# Volterra_MKS_Gen_Daughter_Board.net
KiCad netlist of a schematic drawn in EAGLE
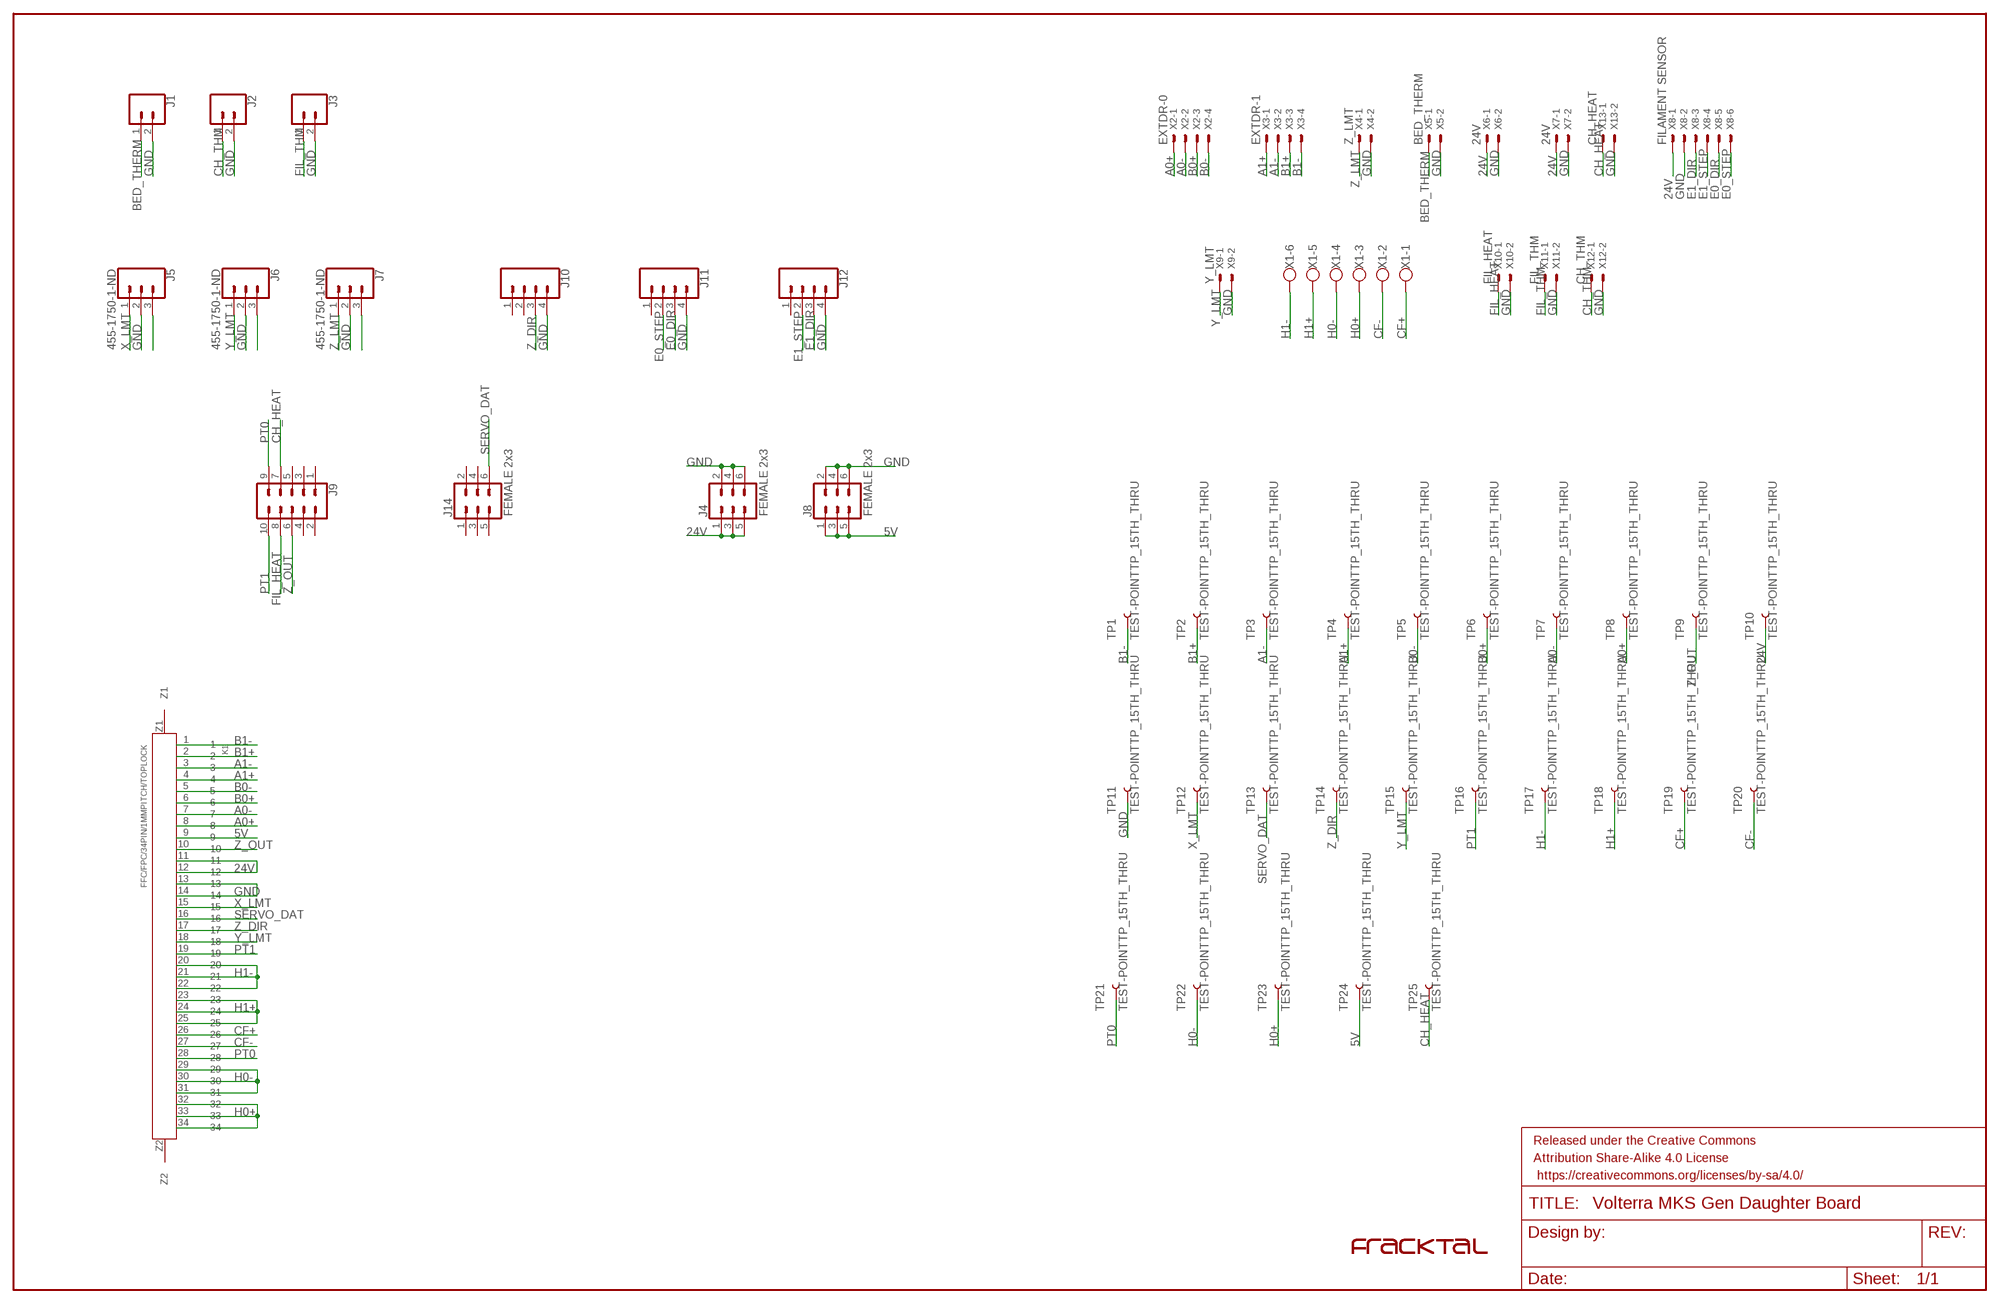
[diagram p0: schematic, sheet 1]

(export (version "E")
  (design (tool "Eeschema 10.0.6"))
  (components
    (comp (ref "FRAME1")
      (value "FRAME-LEDGER")
      (footprint "eagle-import:CREATIVE_COMMONS")
      (libsource (lib "eagle-import") (part "FRAME-LEDGER"))
    )
    (comp (ref "J1")
      (value "CONN_02")
      (footprint "eagle-import:1X02")
      (libsource (lib "eagle-import") (part "CONN_02"))
    )
    (comp (ref "J2")
      (value "CONN_02")
      (footprint "eagle-import:1X02")
      (libsource (lib "eagle-import") (part "CONN_02"))
    )
    (comp (ref "J3")
      (value "CONN_02")
      (footprint "eagle-import:1X02")
      (libsource (lib "eagle-import") (part "CONN_02"))
    )
    (comp (ref "J4")
      (value "FEMALE 2x3")
      (footprint "eagle-import:2X3")
      (libsource (lib "eagle-import") (part "CONN_03X2FEMALE"))
    )
    (comp (ref "J5")
      (value "455-1750-1-ND")
      (footprint "eagle-import:1X03")
      (libsource (lib "eagle-import") (part "CONN_03"))
    )
    (comp (ref "J6")
      (value "455-1750-1-ND")
      (footprint "eagle-import:1X03")
      (libsource (lib "eagle-import") (part "CONN_03"))
    )
    (comp (ref "J7")
      (value "455-1750-1-ND")
      (footprint "eagle-import:1X03")
      (libsource (lib "eagle-import") (part "CONN_03"))
    )
    (comp (ref "J8")
      (value "FEMALE 2x3")
      (footprint "eagle-import:2X3")
      (libsource (lib "eagle-import") (part "CONN_03X2FEMALE"))
    )
    (comp (ref "J9")
      (value "CONN_05X2PTH")
      (footprint "eagle-import:2X5")
      (libsource (lib "eagle-import") (part "CONN_05X2PTH"))
    )
    (comp (ref "J10")
      (value "CONN_04")
      (footprint "eagle-import:1X04")
      (libsource (lib "eagle-import") (part "CONN_04"))
    )
    (comp (ref "J11")
      (value "CONN_04")
      (footprint "eagle-import:1X04")
      (libsource (lib "eagle-import") (part "CONN_04"))
    )
    (comp (ref "J12")
      (value "CONN_04")
      (footprint "eagle-import:1X04")
      (libsource (lib "eagle-import") (part "CONN_04"))
    )
    (comp (ref "J14")
      (value "FEMALE 2x3")
      (footprint "eagle-import:2X3")
      (libsource (lib "eagle-import") (part "CONN_03X2FEMALE"))
    )
    (comp (ref "K1")
      (value "FFC/FPC/34PIN/1MMPITCH/TOPLOCK")
      (footprint "eagle-import:34PIN_1MMPITCH_FFC_FPC")
      (libsource (lib "eagle-import") (part "FFC/FPC/34PIN/1MMPITCH/TOPLOCK"))
    )
    (comp (ref "TP1")
      (value "TEST-POINTTP_15TH_THRU")
      (footprint "eagle-import:TP_15TH")
      (libsource (lib "eagle-import") (part "TEST-POINTTP_15TH_THRU"))
    )
    (comp (ref "TP2")
      (value "TEST-POINTTP_15TH_THRU")
      (footprint "eagle-import:TP_15TH")
      (libsource (lib "eagle-import") (part "TEST-POINTTP_15TH_THRU"))
    )
    (comp (ref "TP3")
      (value "TEST-POINTTP_15TH_THRU")
      (footprint "eagle-import:TP_15TH")
      (libsource (lib "eagle-import") (part "TEST-POINTTP_15TH_THRU"))
    )
    (comp (ref "TP4")
      (value "TEST-POINTTP_15TH_THRU")
      (footprint "eagle-import:TP_15TH")
      (libsource (lib "eagle-import") (part "TEST-POINTTP_15TH_THRU"))
    )
    (comp (ref "TP5")
      (value "TEST-POINTTP_15TH_THRU")
      (footprint "eagle-import:TP_15TH")
      (libsource (lib "eagle-import") (part "TEST-POINTTP_15TH_THRU"))
    )
    (comp (ref "TP6")
      (value "TEST-POINTTP_15TH_THRU")
      (footprint "eagle-import:TP_15TH")
      (libsource (lib "eagle-import") (part "TEST-POINTTP_15TH_THRU"))
    )
    (comp (ref "TP7")
      (value "TEST-POINTTP_15TH_THRU")
      (footprint "eagle-import:TP_15TH")
      (libsource (lib "eagle-import") (part "TEST-POINTTP_15TH_THRU"))
    )
    (comp (ref "TP8")
      (value "TEST-POINTTP_15TH_THRU")
      (footprint "eagle-import:TP_15TH")
      (libsource (lib "eagle-import") (part "TEST-POINTTP_15TH_THRU"))
    )
    (comp (ref "TP9")
      (value "TEST-POINTTP_15TH_THRU")
      (footprint "eagle-import:TP_15TH")
      (libsource (lib "eagle-import") (part "TEST-POINTTP_15TH_THRU"))
    )
    (comp (ref "TP10")
      (value "TEST-POINTTP_15TH_THRU")
      (footprint "eagle-import:TP_15TH")
      (libsource (lib "eagle-import") (part "TEST-POINTTP_15TH_THRU"))
    )
    (comp (ref "TP11")
      (value "TEST-POINTTP_15TH_THRU")
      (footprint "eagle-import:TP_15TH")
      (libsource (lib "eagle-import") (part "TEST-POINTTP_15TH_THRU"))
    )
    (comp (ref "TP12")
      (value "TEST-POINTTP_15TH_THRU")
      (footprint "eagle-import:TP_15TH")
      (libsource (lib "eagle-import") (part "TEST-POINTTP_15TH_THRU"))
    )
    (comp (ref "TP13")
      (value "TEST-POINTTP_15TH_THRU")
      (footprint "eagle-import:TP_15TH")
      (libsource (lib "eagle-import") (part "TEST-POINTTP_15TH_THRU"))
    )
    (comp (ref "TP14")
      (value "TEST-POINTTP_15TH_THRU")
      (footprint "eagle-import:TP_15TH")
      (libsource (lib "eagle-import") (part "TEST-POINTTP_15TH_THRU"))
    )
    (comp (ref "TP15")
      (value "TEST-POINTTP_15TH_THRU")
      (footprint "eagle-import:TP_15TH")
      (libsource (lib "eagle-import") (part "TEST-POINTTP_15TH_THRU"))
    )
    (comp (ref "TP16")
      (value "TEST-POINTTP_15TH_THRU")
      (footprint "eagle-import:TP_15TH")
      (libsource (lib "eagle-import") (part "TEST-POINTTP_15TH_THRU"))
    )
    (comp (ref "TP17")
      (value "TEST-POINTTP_15TH_THRU")
      (footprint "eagle-import:TP_15TH")
      (libsource (lib "eagle-import") (part "TEST-POINTTP_15TH_THRU"))
    )
    (comp (ref "TP18")
      (value "TEST-POINTTP_15TH_THRU")
      (footprint "eagle-import:TP_15TH")
      (libsource (lib "eagle-import") (part "TEST-POINTTP_15TH_THRU"))
    )
    (comp (ref "TP19")
      (value "TEST-POINTTP_15TH_THRU")
      (footprint "eagle-import:TP_15TH")
      (libsource (lib "eagle-import") (part "TEST-POINTTP_15TH_THRU"))
    )
    (comp (ref "TP20")
      (value "TEST-POINTTP_15TH_THRU")
      (footprint "eagle-import:TP_15TH")
      (libsource (lib "eagle-import") (part "TEST-POINTTP_15TH_THRU"))
    )
    (comp (ref "TP21")
      (value "TEST-POINTTP_15TH_THRU")
      (footprint "eagle-import:TP_15TH")
      (libsource (lib "eagle-import") (part "TEST-POINTTP_15TH_THRU"))
    )
    (comp (ref "TP22")
      (value "TEST-POINTTP_15TH_THRU")
      (footprint "eagle-import:TP_15TH")
      (libsource (lib "eagle-import") (part "TEST-POINTTP_15TH_THRU"))
    )
    (comp (ref "TP23")
      (value "TEST-POINTTP_15TH_THRU")
      (footprint "eagle-import:TP_15TH")
      (libsource (lib "eagle-import") (part "TEST-POINTTP_15TH_THRU"))
    )
    (comp (ref "TP24")
      (value "TEST-POINTTP_15TH_THRU")
      (footprint "eagle-import:TP_15TH")
      (libsource (lib "eagle-import") (part "TEST-POINTTP_15TH_THRU"))
    )
    (comp (ref "TP25")
      (value "TEST-POINTTP_15TH_THRU")
      (footprint "eagle-import:TP_15TH")
      (libsource (lib "eagle-import") (part "TEST-POINTTP_15TH_THRU"))
    )
    (comp (ref "U$1")
      (value "FRACKTALLOGO")
      (footprint "eagle-import:FRACKTALLOGO")
      (libsource (lib "eagle-import") (part "FRACKTALLOGO"))
    )
    (comp (ref "X1")
      (value "W237-6")
      (footprint "eagle-import:W237-6")
      (libsource (lib "eagle-import") (part "W237-6"))
    )
    (comp (ref "X2")
      (value "EXTDR-0")
      (footprint "eagle-import:JST-XH-04-PACKAGE-LONG-PAD")
      (libsource (lib "eagle-import") (part "JST-XH-04-PIN-LONG-PAD"))
    )
    (comp (ref "X3")
      (value "EXTDR-1")
      (footprint "eagle-import:JST-XH-04-PACKAGE-LONG-PAD")
      (libsource (lib "eagle-import") (part "JST-XH-04-PIN-LONG-PAD"))
    )
    (comp (ref "X4")
      (value "Z_LMT")
      (footprint "eagle-import:JST-XH-02-PACKAGE-LONG-PAD")
      (libsource (lib "eagle-import") (part "JST-XH-02-PIN-LONG-PAD"))
    )
    (comp (ref "X5")
      (value "BED_THERM")
      (footprint "eagle-import:JST-XH-02-PACKAGE-LONG-PAD")
      (libsource (lib "eagle-import") (part "JST-XH-02-PIN-LONG-PAD"))
    )
    (comp (ref "X6")
      (value "24V")
      (footprint "eagle-import:JST-XH-02-PACKAGE-LONG-PAD")
      (libsource (lib "eagle-import") (part "JST-XH-02-PIN-LONG-PAD"))
    )
    (comp (ref "X7")
      (value "24V")
      (footprint "eagle-import:JST-XH-02-PACKAGE-LONG-PAD")
      (libsource (lib "eagle-import") (part "JST-XH-02-PIN-LONG-PAD"))
    )
    (comp (ref "X8")
      (value "FILAMENT SENSOR")
      (footprint "eagle-import:JST-XH-06-PACKAGE-LONG-PAD")
      (libsource (lib "eagle-import") (part "JST-XH-06-PIN-LONG-PAD"))
    )
    (comp (ref "X9")
      (value "Y_LMT")
      (footprint "eagle-import:JST-XH-02-PACKAGE-LONG-PAD")
      (libsource (lib "eagle-import") (part "JST-XH-02-PIN-LONG-PAD"))
    )
    (comp (ref "X10")
      (value "FIL_HEAT")
      (footprint "eagle-import:JST-XH-02-PACKAGE-LONG-PAD")
      (libsource (lib "eagle-import") (part "JST-XH-02-PIN-LONG-PAD"))
    )
    (comp (ref "X11")
      (value "FIL_THM")
      (footprint "eagle-import:JST-XH-02-PACKAGE-LONG-PAD")
      (libsource (lib "eagle-import") (part "JST-XH-02-PIN-LONG-PAD"))
    )
    (comp (ref "X12")
      (value "CH_THM")
      (footprint "eagle-import:JST-XH-02-PACKAGE-LONG-PAD")
      (libsource (lib "eagle-import") (part "JST-XH-02-PIN-LONG-PAD"))
    )
    (comp (ref "X13")
      (value "CH_HEAT")
      (footprint "eagle-import:JST-XH-02-PACKAGE-LONG-PAD")
      (libsource (lib "eagle-import") (part "JST-XH-02-PIN-LONG-PAD"))
    )
  )
  (nets
    (net (code "1") (name "/5V") (class "Default")
      (node (ref "J8") (pin "1") (pinfunction "1_1") (pintype "bidirectional"))
      (node (ref "J8") (pin "3") (pinfunction "3_3") (pintype "bidirectional"))
      (node (ref "J8") (pin "5") (pinfunction "5_5") (pintype "bidirectional"))
      (node (ref "K1") (pin "9") (pinfunction "9_9") (pintype "bidirectional"))
      (node (ref "TP24") (pin "P$1") (pinfunction "1_P$1") (pintype "bidirectional"))
    )
    (net (code "2") (name "/24V") (class "Default")
      (node (ref "J4") (pin "1") (pinfunction "1_1") (pintype "bidirectional"))
      (node (ref "J4") (pin "3") (pinfunction "3_3") (pintype "bidirectional"))
      (node (ref "J4") (pin "5") (pinfunction "5_5") (pintype "bidirectional"))
      (node (ref "K1") (pin "11") (pinfunction "11_11") (pintype "bidirectional"))
      (node (ref "K1") (pin "12") (pinfunction "12_12") (pintype "bidirectional"))
      (node (ref "TP10") (pin "P$1") (pinfunction "1_P$1") (pintype "bidirectional"))
      (node (ref "X6") (pin "1") (pinfunction "S_1") (pintype "passive"))
      (node (ref "X7") (pin "1") (pinfunction "S_1") (pintype "passive"))
      (node (ref "X8") (pin "1") (pinfunction "S_1") (pintype "passive"))
    )
    (net (code "3") (name "/A0+") (class "Default")
      (node (ref "K1") (pin "8") (pinfunction "8_8") (pintype "bidirectional"))
      (node (ref "TP8") (pin "P$1") (pinfunction "1_P$1") (pintype "bidirectional"))
      (node (ref "X2") (pin "1") (pinfunction "S_1") (pintype "passive"))
    )
    (net (code "4") (name "/A0-") (class "Default")
      (node (ref "K1") (pin "7") (pinfunction "7_7") (pintype "bidirectional"))
      (node (ref "TP7") (pin "P$1") (pinfunction "1_P$1") (pintype "bidirectional"))
      (node (ref "X2") (pin "2") (pinfunction "S_2") (pintype "passive"))
    )
    (net (code "5") (name "/A1+") (class "Default")
      (node (ref "K1") (pin "4") (pinfunction "4_4") (pintype "bidirectional"))
      (node (ref "TP4") (pin "P$1") (pinfunction "1_P$1") (pintype "bidirectional"))
      (node (ref "X3") (pin "1") (pinfunction "S_1") (pintype "passive"))
    )
    (net (code "6") (name "/A1-") (class "Default")
      (node (ref "K1") (pin "3") (pinfunction "3_3") (pintype "bidirectional"))
      (node (ref "TP3") (pin "P$1") (pinfunction "1_P$1") (pintype "bidirectional"))
      (node (ref "X3") (pin "2") (pinfunction "S_2") (pintype "passive"))
    )
    (net (code "7") (name "/B0+") (class "Default")
      (node (ref "K1") (pin "6") (pinfunction "6_6") (pintype "bidirectional"))
      (node (ref "TP6") (pin "P$1") (pinfunction "1_P$1") (pintype "bidirectional"))
      (node (ref "X2") (pin "3") (pinfunction "S_3") (pintype "passive"))
    )
    (net (code "8") (name "/B0-") (class "Default")
      (node (ref "K1") (pin "5") (pinfunction "5_5") (pintype "bidirectional"))
      (node (ref "TP5") (pin "P$1") (pinfunction "1_P$1") (pintype "bidirectional"))
      (node (ref "X2") (pin "4") (pinfunction "S_4") (pintype "passive"))
    )
    (net (code "9") (name "/B1+") (class "Default")
      (node (ref "K1") (pin "2") (pinfunction "2_2") (pintype "bidirectional"))
      (node (ref "TP2") (pin "P$1") (pinfunction "1_P$1") (pintype "bidirectional"))
      (node (ref "X3") (pin "3") (pinfunction "S_3") (pintype "passive"))
    )
    (net (code "10") (name "/B1-") (class "Default")
      (node (ref "K1") (pin "1") (pinfunction "1_1") (pintype "bidirectional"))
      (node (ref "TP1") (pin "P$1") (pinfunction "1_P$1") (pintype "bidirectional"))
      (node (ref "X3") (pin "4") (pinfunction "S_4") (pintype "passive"))
    )
    (net (code "11") (name "/BED_THERM") (class "Default")
      (node (ref "J1") (pin "1") (pinfunction "1_1") (pintype "passive"))
      (node (ref "X5") (pin "1") (pinfunction "S_1") (pintype "passive"))
    )
    (net (code "12") (name "/CF+") (class "Default")
      (node (ref "K1") (pin "26") (pinfunction "26_26") (pintype "bidirectional"))
      (node (ref "TP19") (pin "P$1") (pinfunction "1_P$1") (pintype "bidirectional"))
      (node (ref "X1") (pin "1") (pinfunction "KL_1") (pintype "passive"))
    )
    (net (code "13") (name "/CF-") (class "Default")
      (node (ref "K1") (pin "27") (pinfunction "27_27") (pintype "bidirectional"))
      (node (ref "TP20") (pin "P$1") (pinfunction "1_P$1") (pintype "bidirectional"))
      (node (ref "X1") (pin "2") (pinfunction "KL_2") (pintype "passive"))
    )
    (net (code "14") (name "/CH_HEAT") (class "Default")
      (node (ref "J9") (pin "7") (pinfunction "7_7") (pintype "passive"))
      (node (ref "TP25") (pin "P$1") (pinfunction "1_P$1") (pintype "bidirectional"))
      (node (ref "X13") (pin "1") (pinfunction "S_1") (pintype "passive"))
    )
    (net (code "15") (name "/CH_THM") (class "Default")
      (node (ref "J2") (pin "1") (pinfunction "1_1") (pintype "passive"))
      (node (ref "X12") (pin "1") (pinfunction "S_1") (pintype "passive"))
    )
    (net (code "16") (name "/E0_DIR") (class "Default")
      (node (ref "J11") (pin "3") (pinfunction "3_3") (pintype "passive"))
      (node (ref "X8") (pin "5") (pinfunction "S_5") (pintype "passive"))
    )
    (net (code "17") (name "/E0_STEP") (class "Default")
      (node (ref "J11") (pin "2") (pinfunction "2_2") (pintype "passive"))
      (node (ref "X8") (pin "6") (pinfunction "S_6") (pintype "passive"))
    )
    (net (code "18") (name "/E1_DIR") (class "Default")
      (node (ref "J12") (pin "3") (pinfunction "3_3") (pintype "passive"))
      (node (ref "X8") (pin "3") (pinfunction "S_3") (pintype "passive"))
    )
    (net (code "19") (name "/E1_STEP") (class "Default")
      (node (ref "J12") (pin "2") (pinfunction "2_2") (pintype "passive"))
      (node (ref "X8") (pin "4") (pinfunction "S_4") (pintype "passive"))
    )
    (net (code "20") (name "/FIL_HEAT") (class "Default")
      (node (ref "J9") (pin "8") (pinfunction "8_8") (pintype "passive"))
      (node (ref "X10") (pin "1") (pinfunction "S_1") (pintype "passive"))
    )
    (net (code "21") (name "/FIL_THM") (class "Default")
      (node (ref "J3") (pin "1") (pinfunction "1_1") (pintype "passive"))
      (node (ref "X11") (pin "1") (pinfunction "S_1") (pintype "passive"))
    )
    (net (code "22") (name "/GND") (class "Default")
      (node (ref "J1") (pin "2") (pinfunction "2_2") (pintype "passive"))
      (node (ref "J10") (pin "4") (pinfunction "4_4") (pintype "passive"))
      (node (ref "J11") (pin "4") (pinfunction "4_4") (pintype "passive"))
      (node (ref "J12") (pin "4") (pinfunction "4_4") (pintype "passive"))
      (node (ref "J2") (pin "2") (pinfunction "2_2") (pintype "passive"))
      (node (ref "J3") (pin "2") (pinfunction "2_2") (pintype "passive"))
      (node (ref "J4") (pin "2") (pinfunction "2_2") (pintype "bidirectional"))
      (node (ref "J4") (pin "4") (pinfunction "4_4") (pintype "bidirectional"))
      (node (ref "J4") (pin "6") (pinfunction "6_6") (pintype "bidirectional"))
      (node (ref "J5") (pin "2") (pinfunction "2_2") (pintype "passive"))
      (node (ref "J6") (pin "2") (pinfunction "2_2") (pintype "passive"))
      (node (ref "J7") (pin "2") (pinfunction "2_2") (pintype "passive"))
      (node (ref "J8") (pin "2") (pinfunction "2_2") (pintype "bidirectional"))
      (node (ref "J8") (pin "4") (pinfunction "4_4") (pintype "bidirectional"))
      (node (ref "J8") (pin "6") (pinfunction "6_6") (pintype "bidirectional"))
      (node (ref "K1") (pin "13") (pinfunction "13_13") (pintype "bidirectional"))
      (node (ref "K1") (pin "14") (pinfunction "14_14") (pintype "bidirectional"))
      (node (ref "TP11") (pin "P$1") (pinfunction "1_P$1") (pintype "bidirectional"))
      (node (ref "X10") (pin "2") (pinfunction "S_2") (pintype "passive"))
      (node (ref "X11") (pin "2") (pinfunction "S_2") (pintype "passive"))
      (node (ref "X12") (pin "2") (pinfunction "S_2") (pintype "passive"))
      (node (ref "X13") (pin "2") (pinfunction "S_2") (pintype "passive"))
      (node (ref "X4") (pin "2") (pinfunction "S_2") (pintype "passive"))
      (node (ref "X5") (pin "2") (pinfunction "S_2") (pintype "passive"))
      (node (ref "X6") (pin "2") (pinfunction "S_2") (pintype "passive"))
      (node (ref "X7") (pin "2") (pinfunction "S_2") (pintype "passive"))
      (node (ref "X8") (pin "2") (pinfunction "S_2") (pintype "passive"))
      (node (ref "X9") (pin "2") (pinfunction "S_2") (pintype "passive"))
    )
    (net (code "23") (name "/H0+") (class "Default")
      (node (ref "K1") (pin "32") (pinfunction "32_32") (pintype "bidirectional"))
      (node (ref "K1") (pin "33") (pinfunction "33_33") (pintype "bidirectional"))
      (node (ref "K1") (pin "34") (pinfunction "34_34") (pintype "bidirectional"))
      (node (ref "TP23") (pin "P$1") (pinfunction "1_P$1") (pintype "bidirectional"))
      (node (ref "X1") (pin "3") (pinfunction "KL_3") (pintype "passive"))
    )
    (net (code "24") (name "/H0-") (class "Default")
      (node (ref "K1") (pin "29") (pinfunction "29_29") (pintype "bidirectional"))
      (node (ref "K1") (pin "30") (pinfunction "30_30") (pintype "bidirectional"))
      (node (ref "K1") (pin "31") (pinfunction "31_31") (pintype "bidirectional"))
      (node (ref "TP22") (pin "P$1") (pinfunction "1_P$1") (pintype "bidirectional"))
      (node (ref "X1") (pin "4") (pinfunction "KL_4") (pintype "passive"))
    )
    (net (code "25") (name "/H1+") (class "Default")
      (node (ref "K1") (pin "23") (pinfunction "23_23") (pintype "bidirectional"))
      (node (ref "K1") (pin "24") (pinfunction "24_24") (pintype "bidirectional"))
      (node (ref "K1") (pin "25") (pinfunction "25_25") (pintype "bidirectional"))
      (node (ref "TP18") (pin "P$1") (pinfunction "1_P$1") (pintype "bidirectional"))
      (node (ref "X1") (pin "5") (pinfunction "KL_5") (pintype "passive"))
    )
    (net (code "26") (name "/H1-") (class "Default")
      (node (ref "K1") (pin "20") (pinfunction "20_20") (pintype "bidirectional"))
      (node (ref "K1") (pin "21") (pinfunction "21_21") (pintype "bidirectional"))
      (node (ref "K1") (pin "22") (pinfunction "22_22") (pintype "bidirectional"))
      (node (ref "TP17") (pin "P$1") (pinfunction "1_P$1") (pintype "bidirectional"))
      (node (ref "X1") (pin "6") (pinfunction "KL_6") (pintype "passive"))
    )
    (net (code "27") (name "/PT0") (class "Default")
      (node (ref "J9") (pin "9") (pinfunction "9_9") (pintype "passive"))
      (node (ref "K1") (pin "28") (pinfunction "28_28") (pintype "bidirectional"))
      (node (ref "TP21") (pin "P$1") (pinfunction "1_P$1") (pintype "bidirectional"))
    )
    (net (code "28") (name "/PT1") (class "Default")
      (node (ref "J9") (pin "10") (pinfunction "10_10") (pintype "passive"))
      (node (ref "K1") (pin "19") (pinfunction "19_19") (pintype "bidirectional"))
      (node (ref "TP16") (pin "P$1") (pinfunction "1_P$1") (pintype "bidirectional"))
    )
    (net (code "29") (name "/SERVO_DAT") (class "Default")
      (node (ref "J14") (pin "6") (pinfunction "6_6") (pintype "bidirectional"))
      (node (ref "K1") (pin "16") (pinfunction "16_16") (pintype "bidirectional"))
      (node (ref "TP13") (pin "P$1") (pinfunction "1_P$1") (pintype "bidirectional"))
    )
    (net (code "30") (name "/X_LMT") (class "Default")
      (node (ref "J5") (pin "1") (pinfunction "1_1") (pintype "passive"))
      (node (ref "K1") (pin "15") (pinfunction "15_15") (pintype "bidirectional"))
      (node (ref "TP12") (pin "P$1") (pinfunction "1_P$1") (pintype "bidirectional"))
    )
    (net (code "31") (name "/Y_LMT") (class "Default")
      (node (ref "J6") (pin "1") (pinfunction "1_1") (pintype "passive"))
      (node (ref "K1") (pin "18") (pinfunction "18_18") (pintype "bidirectional"))
      (node (ref "TP15") (pin "P$1") (pinfunction "1_P$1") (pintype "bidirectional"))
      (node (ref "X9") (pin "1") (pinfunction "S_1") (pintype "passive"))
    )
    (net (code "32") (name "/Z_DIR") (class "Default")
      (node (ref "J10") (pin "3") (pinfunction "3_3") (pintype "passive"))
      (node (ref "K1") (pin "17") (pinfunction "17_17") (pintype "bidirectional"))
      (node (ref "TP14") (pin "P$1") (pinfunction "1_P$1") (pintype "bidirectional"))
    )
    (net (code "33") (name "/Z_LMT") (class "Default")
      (node (ref "J7") (pin "1") (pinfunction "1_1") (pintype "passive"))
      (node (ref "X4") (pin "1") (pinfunction "S_1") (pintype "passive"))
    )
    (net (code "34") (name "/Z_OUT") (class "Default")
      (node (ref "J9") (pin "6") (pinfunction "6_6") (pintype "passive"))
      (node (ref "K1") (pin "10") (pinfunction "10_10") (pintype "bidirectional"))
      (node (ref "TP9") (pin "P$1") (pinfunction "1_P$1") (pintype "bidirectional"))
    )
    (net (code "35") (name "unconnected-(J5-Pad3)") (class "Default")
      (node (ref "J5") (pin "3") (pinfunction "3_3") (pintype "passive"))
    )
    (net (code "36") (name "unconnected-(J6-Pad3)") (class "Default")
      (node (ref "J6") (pin "3") (pinfunction "3_3") (pintype "passive"))
    )
    (net (code "37") (name "unconnected-(J7-Pad3)") (class "Default")
      (node (ref "J7") (pin "3") (pinfunction "3_3") (pintype "passive"))
    )
    (net (code "38") (name "unconnected-(J9-Pad1)") (class "Default")
      (node (ref "J9") (pin "1") (pinfunction "1_1") (pintype "passive"))
    )
    (net (code "39") (name "unconnected-(J9-Pad2)") (class "Default")
      (node (ref "J9") (pin "2") (pinfunction "2_2") (pintype "passive"))
    )
    (net (code "40") (name "unconnected-(J9-Pad3)") (class "Default")
      (node (ref "J9") (pin "3") (pinfunction "3_3") (pintype "passive"))
    )
    (net (code "41") (name "unconnected-(J9-Pad4)") (class "Default")
      (node (ref "J9") (pin "4") (pinfunction "4_4") (pintype "passive"))
    )
    (net (code "42") (name "unconnected-(J9-Pad5)") (class "Default")
      (node (ref "J9") (pin "5") (pinfunction "5_5") (pintype "passive"))
    )
    (net (code "43") (name "unconnected-(J10-Pad1)") (class "Default")
      (node (ref "J10") (pin "1") (pinfunction "1_1") (pintype "passive"))
    )
    (net (code "44") (name "unconnected-(J10-Pad2)") (class "Default")
      (node (ref "J10") (pin "2") (pinfunction "2_2") (pintype "passive"))
    )
    (net (code "45") (name "unconnected-(J11-Pad1)") (class "Default")
      (node (ref "J11") (pin "1") (pinfunction "1_1") (pintype "passive"))
    )
    (net (code "46") (name "unconnected-(J12-Pad1)") (class "Default")
      (node (ref "J12") (pin "1") (pinfunction "1_1") (pintype "passive"))
    )
    (net (code "47") (name "unconnected-(J14-Pad1)") (class "Default")
      (node (ref "J14") (pin "1") (pinfunction "1_1") (pintype "bidirectional"))
    )
    (net (code "48") (name "unconnected-(J14-Pad2)") (class "Default")
      (node (ref "J14") (pin "2") (pinfunction "2_2") (pintype "bidirectional"))
    )
    (net (code "49") (name "unconnected-(J14-Pad3)") (class "Default")
      (node (ref "J14") (pin "3") (pinfunction "3_3") (pintype "bidirectional"))
    )
    (net (code "50") (name "unconnected-(J14-Pad4)") (class "Default")
      (node (ref "J14") (pin "4") (pinfunction "4_4") (pintype "bidirectional"))
    )
    (net (code "51") (name "unconnected-(J14-Pad5)") (class "Default")
      (node (ref "J14") (pin "5") (pinfunction "5_5") (pintype "bidirectional"))
    )
    (net (code "52") (name "unconnected-(K1-PadZ1)") (class "Default")
      (node (ref "K1") (pin "Z1") (pinfunction "Z1_Z1") (pintype "bidirectional"))
    )
    (net (code "53") (name "unconnected-(K1-PadZ2)") (class "Default")
      (node (ref "K1") (pin "Z2") (pinfunction "Z2_Z2") (pintype "bidirectional"))
    )
  )
)
